# Peripheral.net
KiCad netlist of a schematic drawn in Altium Designer
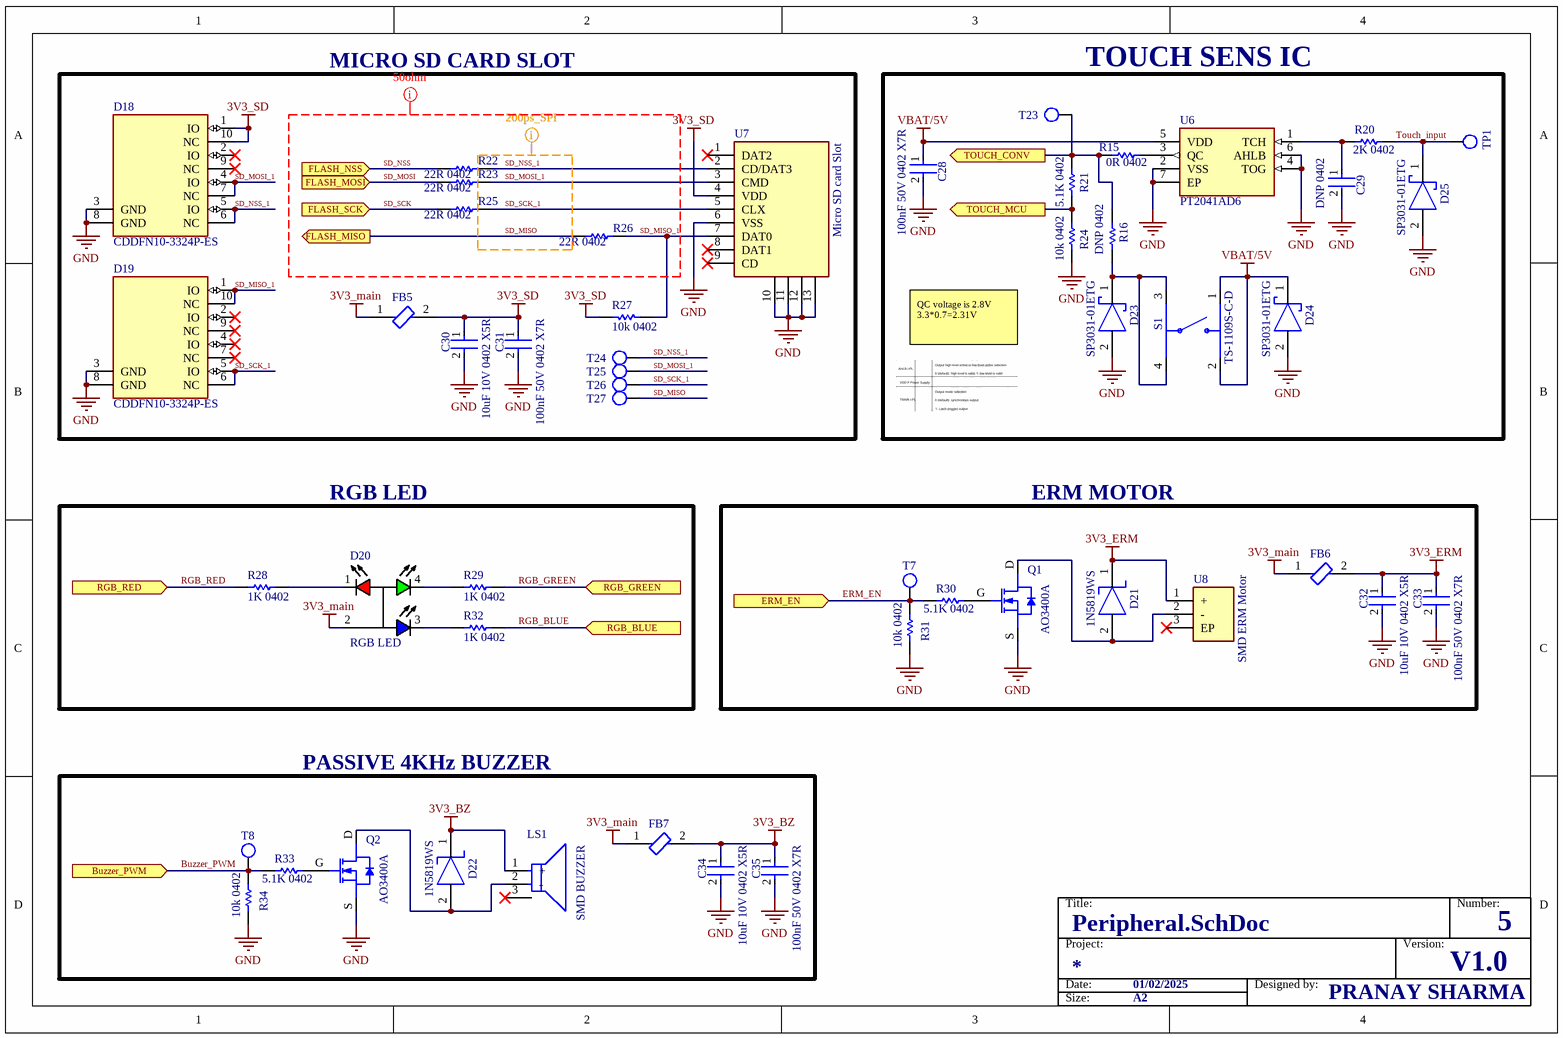
[diagram p0: Peripheral.SchDoc]

(export (version "E")
  (design (tool "Eeschema 10.0.6"))
  (components
    (comp (ref "C28")
      (value "100nF 50V 0402 X7R")
      (footprint "Res, Cap, Ind, LED, FB_Lib:0402 IPC CLASS C CAPACITOR")
      (libsource (lib "Capacitor_Lib") (part "100nF 50V 0402 X7R"))
    )
    (comp (ref "C29")
      (value "DNP 0402")
      (footprint "0402 IPC Class C Capacitor")
      (libsource (lib "Integrated Library V1.0") (part "Capacitor 0402"))
    )
    (comp (ref "C30")
      (value "10uF 10V 0402 X5R")
      (footprint "Res, Cap, Ind, LED, FB_Lib:0402 IPC CLASS C CAPACITOR")
      (libsource (lib "Capacitor_Lib") (part "10uF 10V 0402 X5R"))
    )
    (comp (ref "C31")
      (value "100nF 50V 0402 X7R")
      (footprint "Res, Cap, Ind, LED, FB_Lib:0402 IPC CLASS C CAPACITOR")
      (libsource (lib "Capacitor_Lib") (part "100nF 50V 0402 X7R"))
    )
    (comp (ref "C32")
      (value "10uF 10V 0402 X5R")
      (footprint "Res, Cap, Ind, LED, FB_Lib:0402 IPC CLASS C CAPACITOR")
      (libsource (lib "Capacitor_Lib") (part "10uF 10V 0402 X5R"))
    )
    (comp (ref "C33")
      (value "100nF 50V 0402 X7R")
      (footprint "Res, Cap, Ind, LED, FB_Lib:0402 IPC CLASS C CAPACITOR")
      (libsource (lib "Capacitor_Lib") (part "100nF 50V 0402 X7R"))
    )
    (comp (ref "C34")
      (value "10uF 10V 0402 X5R")
      (footprint "Res, Cap, Ind, LED, FB_Lib:0402 IPC CLASS C CAPACITOR")
      (libsource (lib "Capacitor_Lib") (part "10uF 10V 0402 X5R"))
    )
    (comp (ref "C35")
      (value "100nF 50V 0402 X7R")
      (footprint "Res, Cap, Ind, LED, FB_Lib:0402 IPC CLASS C CAPACITOR")
      (libsource (lib "Capacitor_Lib") (part "100nF 50V 0402 X7R"))
    )
    (comp (ref "D18")
      (value "CDDFN10-3324P-ES")
      (footprint "Res, Cap, Ind, LED, FB_Lib:DFN2510D-10 IPC-C")
      (libsource (lib "Diodes_Lib") (part "CDDFN10-3324P-ES"))
    )
    (comp (ref "D19")
      (value "CDDFN10-3324P-ES")
      (footprint "Res, Cap, Ind, LED, FB_Lib:DFN2510D-10 IPC-C")
      (libsource (lib "Diodes_Lib") (part "CDDFN10-3324P-ES"))
    )
    (comp (ref "D20")
      (value "RGB LED")
      (footprint "Res, Cap, Ind, LED, FB_Lib:NH-B1515RGBA-HF IPC-C")
      (libsource (lib "Diodes_Lib") (part "NH-B1515RGBA-HF"))
    )
    (comp (ref "D21")
      (value "1N5819WS")
      (footprint "Res, Cap, Ind, LED, FB_Lib:SOD-323 IPC-C")
      (libsource (lib "Diodes_Lib") (part "1N5819WS"))
    )
    (comp (ref "D22")
      (value "1N5819WS")
      (footprint "Res, Cap, Ind, LED, FB_Lib:SOD-323 IPC-C")
      (libsource (lib "Diodes_Lib") (part "1N5819WS"))
    )
    (comp (ref "D23")
      (value "SP3031-01ETG")
      (footprint "Res, Cap, Ind, LED, FB_Lib:SOD882 IPC-C")
      (libsource (lib "Diodes_Lib") (part "SP3031-01ETG"))
    )
    (comp (ref "D24")
      (value "SP3031-01ETG")
      (footprint "Res, Cap, Ind, LED, FB_Lib:SOD882 IPC-C")
      (libsource (lib "Diodes_Lib") (part "SP3031-01ETG"))
    )
    (comp (ref "D25")
      (value "SP3031-01ETG")
      (footprint "Res, Cap, Ind, LED, FB_Lib:SOD882 IPC-C")
      (libsource (lib "Diodes_Lib") (part "SP3031-01ETG"))
    )
    (comp (ref "FB5")
      (value "BLM15AX102SN1D")
      (footprint "Res, Cap, Ind, LED, FB_Lib:0402 IPC CLASS C FERRITE BEAD")
      (libsource (lib "Ferrite_Bead_Lib") (part "BLM15AX102SN1D"))
    )
    (comp (ref "FB6")
      (value "BLM15AX102SN1D")
      (footprint "Res, Cap, Ind, LED, FB_Lib:0402 IPC CLASS C FERRITE BEAD")
      (libsource (lib "Ferrite_Bead_Lib") (part "BLM15AX102SN1D"))
    )
    (comp (ref "FB7")
      (value "BLM15AX102SN1D")
      (footprint "Res, Cap, Ind, LED, FB_Lib:0402 IPC CLASS C FERRITE BEAD")
      (libsource (lib "Ferrite_Bead_Lib") (part "BLM15AX102SN1D"))
    )
    (comp (ref "LS1")
      (value "SMD BUZZER")
      (footprint "Miscellaneous_Lib:MLT-5020")
      (libsource (lib "Miscellaneous_Lib") (part "MLT-5020"))
    )
    (comp (ref "Q1")
      (value "AO3400A")
      (footprint "Transistors_Lib:SOT-23 IPC-C")
      (libsource (lib "Transistors_Lib") (part "AO3400A"))
    )
    (comp (ref "Q2")
      (value "AO3400A")
      (footprint "Transistors_Lib:SOT-23 IPC-C")
      (libsource (lib "Transistors_Lib") (part "AO3400A"))
    )
    (comp (ref "R15")
      (value "0R 0402")
      (footprint "Res, Cap, Ind, LED, FB_Lib:0402 IPC CLASS B RESISTOR")
      (libsource (lib "Resistor_Lib") (part "0R 1% 0402"))
    )
    (comp (ref "R16")
      (value "DNP 0402")
      (footprint "Res, Cap, Ind, LED, FB_Lib:0402 IPC CLASS B RESISTOR")
      (libsource (lib "Resistor_Lib") (part "0R 1% 0402"))
    )
    (comp (ref "R20")
      (value "2K 0402")
      (footprint "Res, Cap, Ind, LED, FB_Lib:0402 IPC CLASS C RESISTOR")
      (libsource (lib "Resistor_Lib") (part "2K 1% 0402"))
    )
    (comp (ref "R21")
      (value "5.1K 0402")
      (footprint "Res, Cap, Ind, LED, FB_Lib:0402 IPC CLASS C RESISTOR")
      (libsource (lib "Resistor_Lib") (part "5.1K 1% 0402"))
    )
    (comp (ref "R22")
      (value "22R 0402")
      (footprint "Res, Cap, Ind, LED, FB_Lib:0402 IPC CLASS C RESISTOR")
      (libsource (lib "Resistor_Lib") (part "22R 1% 0402"))
    )
    (comp (ref "R23")
      (value "22R 0402")
      (footprint "Res, Cap, Ind, LED, FB_Lib:0402 IPC CLASS C RESISTOR")
      (libsource (lib "Resistor_Lib") (part "22R 1% 0402"))
    )
    (comp (ref "R24")
      (value "10k 0402")
      (footprint "Res, Cap, Ind, LED, FB_Lib:0402 IPC CLASS C RESISTOR")
      (libsource (lib "Resistor_Lib") (part "10k 1% 0402"))
    )
    (comp (ref "R25")
      (value "22R 0402")
      (footprint "Res, Cap, Ind, LED, FB_Lib:0402 IPC CLASS C RESISTOR")
      (libsource (lib "Resistor_Lib") (part "22R 1% 0402"))
    )
    (comp (ref "R26")
      (value "22R 0402")
      (footprint "Res, Cap, Ind, LED, FB_Lib:0402 IPC CLASS C RESISTOR")
      (libsource (lib "Resistor_Lib") (part "22R 1% 0402"))
    )
    (comp (ref "R27")
      (value "10k 0402")
      (footprint "Res, Cap, Ind, LED, FB_Lib:0402 IPC CLASS C RESISTOR")
      (libsource (lib "Resistor_Lib") (part "10k 1% 0402"))
    )
    (comp (ref "R28")
      (value "1K 0402")
      (footprint "Res, Cap, Ind, LED, FB_Lib:0402 IPC CLASS C RESISTOR")
      (libsource (lib "Resistor_Lib") (part "1K 1% 0402"))
    )
    (comp (ref "R29")
      (value "1K 0402")
      (footprint "Res, Cap, Ind, LED, FB_Lib:0402 IPC CLASS C RESISTOR")
      (libsource (lib "Resistor_Lib") (part "1K 1% 0402"))
    )
    (comp (ref "R30")
      (value "5.1K 0402")
      (footprint "Res, Cap, Ind, LED, FB_Lib:0402 IPC CLASS C RESISTOR")
      (libsource (lib "Resistor_Lib") (part "5.1K 1% 0402"))
    )
    (comp (ref "R31")
      (value "10k 0402")
      (footprint "Res, Cap, Ind, LED, FB_Lib:0402 IPC CLASS C RESISTOR")
      (libsource (lib "Resistor_Lib") (part "10k 1% 0402"))
    )
    (comp (ref "R32")
      (value "1K 0402")
      (footprint "Res, Cap, Ind, LED, FB_Lib:0402 IPC CLASS C RESISTOR")
      (libsource (lib "Resistor_Lib") (part "1K 1% 0402"))
    )
    (comp (ref "R33")
      (value "5.1K 0402")
      (footprint "Res, Cap, Ind, LED, FB_Lib:0402 IPC CLASS C RESISTOR")
      (libsource (lib "Resistor_Lib") (part "5.1K 1% 0402"))
    )
    (comp (ref "R34")
      (value "10k 0402")
      (footprint "Res, Cap, Ind, LED, FB_Lib:0402 IPC CLASS C RESISTOR")
      (libsource (lib "Resistor_Lib") (part "10k 1% 0402"))
    )
    (comp (ref "S1")
      (value "TS-1109S-C-D")
      (footprint "TS-1127-C")
      (libsource (lib "Integrated Library V1.0") (part "TS-1127-C"))
    )
    (comp (ref "T7")
      (value "~")
      (footprint "Test Point TH")
      (libsource (lib "Miscellaneous_Lib") (part "Test Point TH"))
    )
    (comp (ref "T8")
      (value "~")
      (footprint "Test Point TH")
      (libsource (lib "Miscellaneous_Lib") (part "Test Point TH"))
    )
    (comp (ref "T23")
      (value "TP")
      (footprint "Miscellaneous_Lib:Testpoint1")
      (libsource (lib "Miscellaneous_Lib") (part "Testpoint1"))
    )
    (comp (ref "T24")
      (value "TP")
      (footprint "Miscellaneous_Lib:Testpoint1")
      (libsource (lib "Miscellaneous_Lib") (part "Testpoint1"))
    )
    (comp (ref "T25")
      (value "TP")
      (footprint "Miscellaneous_Lib:Testpoint1")
      (libsource (lib "Miscellaneous_Lib") (part "Testpoint1"))
    )
    (comp (ref "T26")
      (value "TP")
      (footprint "Miscellaneous_Lib:Testpoint1")
      (libsource (lib "Miscellaneous_Lib") (part "Testpoint1"))
    )
    (comp (ref "T27")
      (value "TP")
      (footprint "Miscellaneous_Lib:Testpoint1")
      (libsource (lib "Miscellaneous_Lib") (part "Testpoint1"))
    )
    (comp (ref "TP1")
      (value "Test Point TH")
      (footprint "Test Point TH")
      (libsource (lib "Integrated Library V1.0") (part "Test Point TH"))
    )
    (comp (ref "U6")
      (value "PT2041AD6")
      (footprint "Integrated_Circuits_Lib:DFN2X2-6L IPC-C")
      (libsource (lib "Integrated_Circuits_Lib") (part "PT2041AD6"))
    )
    (comp (ref "U7")
      (value "Micro SD card Slot")
      (footprint "Connectors_Lib:XKTF-015-G")
      (libsource (lib "Connectors_Lib") (part "XKTF-015-G"))
    )
    (comp (ref "U8")
      (value "SMD ERM Motor")
      (footprint "Miscellaneous_Lib:Z3OC1T8219731")
      (libsource (lib "Miscellaneous_Lib") (part "Z3OC1T8219731"))
    )
  )
  (nets
    (net (code "1") (name "/Buzzer_PWM") (class "Default")
      (node (ref "R33") (pin "1") (pinfunction "1_1") (pintype "passive"))
      (node (ref "R34") (pin "2") (pinfunction "2_2") (pintype "passive"))
      (node (ref "T8") (pin "0") (pinfunction "0_0") (pintype "passive"))
    )
    (net (code "2") (name "/ERM_EN") (class "Default")
      (node (ref "R30") (pin "1") (pinfunction "1_1") (pintype "passive"))
      (node (ref "R31") (pin "2") (pinfunction "2_2") (pintype "passive"))
      (node (ref "T7") (pin "0") (pinfunction "0_0") (pintype "passive"))
    )
    (net (code "3") (name "/RGB_BLUE") (class "Default")
      (node (ref "R32") (pin "2") (pinfunction "2_2") (pintype "passive"))
    )
    (net (code "4") (name "/RGB_GREEN") (class "Default")
      (node (ref "R29") (pin "2") (pinfunction "2_2") (pintype "passive"))
    )
    (net (code "5") (name "/RGB_RED") (class "Default")
      (node (ref "R28") (pin "1") (pinfunction "1_1") (pintype "passive"))
    )
    (net (code "6") (name "/SD_MISO") (class "Default")
      (node (ref "R26") (pin "1") (pinfunction "1_1") (pintype "passive"))
      (node (ref "T27") (pin "0") (pinfunction "0_0") (pintype "passive"))
    )
    (net (code "7") (name "/SD_MISO_1") (class "Default")
      (node (ref "D19") (pin "1") (pinfunction "IO_1") (pintype "bidirectional"))
      (node (ref "D19") (pin "10") (pinfunction "NC_10") (pintype "passive"))
      (node (ref "R26") (pin "2") (pinfunction "2_2") (pintype "passive"))
      (node (ref "R27") (pin "2") (pinfunction "2_2") (pintype "passive"))
      (node (ref "U7") (pin "7") (pinfunction "DAT0_7") (pintype "passive"))
    )
    (net (code "8") (name "/SD_MOSI") (class "Default")
      (node (ref "R23") (pin "1") (pinfunction "1_1") (pintype "passive"))
    )
    (net (code "9") (name "/SD_MOSI_1") (class "Default")
      (node (ref "D18") (pin "4") (pinfunction "IO_4") (pintype "bidirectional"))
      (node (ref "D18") (pin "7") (pinfunction "NC_7") (pintype "passive"))
      (node (ref "R23") (pin "2") (pinfunction "2_2") (pintype "passive"))
      (node (ref "T25") (pin "0") (pinfunction "0_0") (pintype "passive"))
      (node (ref "U7") (pin "3") (pinfunction "CMD_3") (pintype "passive"))
    )
    (net (code "10") (name "/SD_NSS") (class "Default")
      (node (ref "R22") (pin "1") (pinfunction "1_1") (pintype "passive"))
    )
    (net (code "11") (name "/SD_NSS_1") (class "Default")
      (node (ref "D18") (pin "5") (pinfunction "IO_5") (pintype "bidirectional"))
      (node (ref "D18") (pin "6") (pinfunction "NC_6") (pintype "passive"))
      (node (ref "R22") (pin "2") (pinfunction "2_2") (pintype "passive"))
      (node (ref "T24") (pin "0") (pinfunction "0_0") (pintype "passive"))
      (node (ref "U7") (pin "2") (pinfunction "CD/DAT3_2") (pintype "passive"))
    )
    (net (code "12") (name "/SD_SCK") (class "Default")
      (node (ref "R25") (pin "1") (pinfunction "1_1") (pintype "passive"))
    )
    (net (code "13") (name "/SD_SCK_1") (class "Default")
      (node (ref "D19") (pin "5") (pinfunction "IO_5") (pintype "bidirectional"))
      (node (ref "D19") (pin "6") (pinfunction "NC_6") (pintype "passive"))
      (node (ref "R25") (pin "2") (pinfunction "2_2") (pintype "passive"))
      (node (ref "T26") (pin "0") (pinfunction "0_0") (pintype "passive"))
      (node (ref "U7") (pin "5") (pinfunction "CLX_5") (pintype "passive"))
    )
    (net (code "14") (name "/TOUCH_CONV") (class "Default")
      (node (ref "R15") (pin "2") (pinfunction "2_2") (pintype "passive"))
      (node (ref "R16") (pin "1") (pinfunction "1_1") (pintype "passive"))
      (node (ref "R21") (pin "2") (pinfunction "2_2") (pintype "passive"))
      (node (ref "T23") (pin "0") (pinfunction "0_0") (pintype "passive"))
    )
    (net (code "15") (name "/TOUCH_MCU") (class "Default")
      (node (ref "R21") (pin "1") (pinfunction "1_1") (pintype "passive"))
      (node (ref "R24") (pin "1") (pinfunction "1_1") (pintype "passive"))
    )
    (net (code "16") (name "/Touch_input") (class "Default")
      (node (ref "D25") (pin "1") (pinfunction "C_1") (pintype "passive"))
      (node (ref "R20") (pin "2") (pinfunction "2_2") (pintype "passive"))
      (node (ref "TP1") (pin "0") (pinfunction "0_0") (pintype "passive"))
    )
    (net (code "17") (name "3V3_BZ") (class "Default")
      (node (ref "C34") (pin "1") (pinfunction "1_1") (pintype "passive"))
      (node (ref "C35") (pin "1") (pinfunction "1_1") (pintype "passive"))
      (node (ref "D22") (pin "1") (pinfunction "C_1") (pintype "passive"))
      (node (ref "FB7") (pin "2") (pinfunction "2_2") (pintype "passive"))
      (node (ref "LS1") (pin "1") (pinfunction "+_1") (pintype "passive"))
    )
    (net (code "18") (name "3V3_ERM") (class "Default")
      (node (ref "C32") (pin "1") (pinfunction "1_1") (pintype "passive"))
      (node (ref "C33") (pin "1") (pinfunction "1_1") (pintype "passive"))
      (node (ref "D21") (pin "1") (pinfunction "C_1") (pintype "passive"))
      (node (ref "FB6") (pin "2") (pinfunction "2_2") (pintype "passive"))
      (node (ref "U8") (pin "1") (pinfunction "+_1") (pintype "power_in"))
    )
    (net (code "19") (name "3V3_SD") (class "Default")
      (node (ref "C30") (pin "1") (pinfunction "1_1") (pintype "passive"))
      (node (ref "C31") (pin "1") (pinfunction "1_1") (pintype "passive"))
      (node (ref "D18") (pin "1") (pinfunction "IO_1") (pintype "bidirectional"))
      (node (ref "D18") (pin "10") (pinfunction "NC_10") (pintype "passive"))
      (node (ref "FB5") (pin "2") (pinfunction "2_2") (pintype "passive"))
      (node (ref "R27") (pin "1") (pinfunction "1_1") (pintype "passive"))
      (node (ref "U7") (pin "4") (pinfunction "VDD_4") (pintype "passive"))
    )
    (net (code "20") (name "3V3_main") (class "Default")
      (node (ref "D20") (pin "2") (pinfunction "COM+_2") (pintype "passive"))
      (node (ref "FB5") (pin "1") (pinfunction "1_1") (pintype "passive"))
      (node (ref "FB6") (pin "1") (pinfunction "1_1") (pintype "passive"))
      (node (ref "FB7") (pin "1") (pinfunction "1_1") (pintype "passive"))
    )
    (net (code "21") (name "GND") (class "Default")
      (node (ref "C28") (pin "2") (pinfunction "2_2") (pintype "passive"))
      (node (ref "C29") (pin "2") (pinfunction "2_2") (pintype "passive"))
      (node (ref "C30") (pin "2") (pinfunction "2_2") (pintype "passive"))
      (node (ref "C31") (pin "2") (pinfunction "2_2") (pintype "passive"))
      (node (ref "C32") (pin "2") (pinfunction "2_2") (pintype "passive"))
      (node (ref "C33") (pin "2") (pinfunction "2_2") (pintype "passive"))
      (node (ref "C34") (pin "2") (pinfunction "2_2") (pintype "passive"))
      (node (ref "C35") (pin "2") (pinfunction "2_2") (pintype "passive"))
      (node (ref "D18") (pin "3") (pinfunction "GND_3") (pintype "power_in"))
      (node (ref "D18") (pin "8") (pinfunction "GND_8") (pintype "power_in"))
      (node (ref "D19") (pin "3") (pinfunction "GND_3") (pintype "power_in"))
      (node (ref "D19") (pin "8") (pinfunction "GND_8") (pintype "power_in"))
      (node (ref "D23") (pin "2") (pinfunction "A_2") (pintype "passive"))
      (node (ref "D24") (pin "2") (pinfunction "A_2") (pintype "passive"))
      (node (ref "D25") (pin "2") (pinfunction "A_2") (pintype "passive"))
      (node (ref "Q1") (pin "S") (pinfunction "SOURCE_S") (pintype "passive"))
      (node (ref "Q2") (pin "S") (pinfunction "SOURCE_S") (pintype "passive"))
      (node (ref "R24") (pin "2") (pinfunction "2_2") (pintype "passive"))
      (node (ref "R31") (pin "1") (pinfunction "1_1") (pintype "passive"))
      (node (ref "R34") (pin "1") (pinfunction "1_1") (pintype "passive"))
      (node (ref "U6") (pin "2") (pinfunction "VSS_2") (pintype "power_in"))
      (node (ref "U6") (pin "4") (pinfunction "TOG_4") (pintype "input"))
      (node (ref "U6") (pin "6") (pinfunction "AHLB_6") (pintype "input"))
      (node (ref "U6") (pin "7") (pinfunction "EP_7") (pintype "power_in"))
      (node (ref "U7") (pin "10") (pintype "passive"))
      (node (ref "U7") (pin "11") (pintype "passive"))
      (node (ref "U7") (pin "12") (pintype "passive"))
      (node (ref "U7") (pin "13") (pintype "passive"))
      (node (ref "U7") (pin "6") (pinfunction "VSS_6") (pintype "passive"))
    )
    (net (code "22") (name "Net-(D20-B-)") (class "Default")
      (node (ref "D20") (pin "3") (pinfunction "B-_3") (pintype "passive"))
      (node (ref "R32") (pin "1") (pinfunction "1_1") (pintype "passive"))
    )
    (net (code "23") (name "Net-(D20-G-)") (class "Default")
      (node (ref "D20") (pin "4") (pinfunction "G-_4") (pintype "passive"))
      (node (ref "R29") (pin "1") (pinfunction "1_1") (pintype "passive"))
    )
    (net (code "24") (name "Net-(D20-R-)") (class "Default")
      (node (ref "D20") (pin "1") (pinfunction "R-_1") (pintype "passive"))
      (node (ref "R28") (pin "2") (pinfunction "2_2") (pintype "passive"))
    )
    (net (code "25") (name "Net-(D21-A)") (class "Default")
      (node (ref "D21") (pin "2") (pinfunction "A_2") (pintype "passive"))
      (node (ref "Q1") (pin "D") (pinfunction "DRAIN_D") (pintype "passive"))
      (node (ref "U8") (pin "2") (pinfunction "-_2") (pintype "power_in"))
    )
    (net (code "26") (name "Net-(D22-A)") (class "Default")
      (node (ref "D22") (pin "2") (pinfunction "A_2") (pintype "passive"))
      (node (ref "LS1") (pin "2") (pinfunction "-_2") (pintype "passive"))
      (node (ref "Q2") (pin "D") (pinfunction "DRAIN_D") (pintype "passive"))
    )
    (net (code "27") (name "Net-(D23-C)") (class "Default")
      (node (ref "D23") (pin "1") (pinfunction "C_1") (pintype "passive"))
      (node (ref "R16") (pin "2") (pinfunction "2_2") (pintype "passive"))
      (node (ref "S1") (pin "3") (pinfunction "3_3") (pintype "passive"))
      (node (ref "S1") (pin "4") (pinfunction "4_4") (pintype "passive"))
    )
    (net (code "28") (name "Net-(Q1-GATE)") (class "Default")
      (node (ref "Q1") (pin "G") (pinfunction "GATE_G") (pintype "passive"))
      (node (ref "R30") (pin "2") (pinfunction "2_2") (pintype "passive"))
    )
    (net (code "29") (name "Net-(Q2-GATE)") (class "Default")
      (node (ref "Q2") (pin "G") (pinfunction "GATE_G") (pintype "passive"))
      (node (ref "R33") (pin "2") (pinfunction "2_2") (pintype "passive"))
    )
    (net (code "30") (name "Net-(U6-QC)") (class "Default")
      (node (ref "R15") (pin "1") (pinfunction "1_1") (pintype "passive"))
      (node (ref "U6") (pin "3") (pinfunction "QC_3") (pintype "output"))
    )
    (net (code "31") (name "Net-(U6-TCH)") (class "Default")
      (node (ref "C29") (pin "1") (pinfunction "1_1") (pintype "passive"))
      (node (ref "R20") (pin "1") (pinfunction "1_1") (pintype "passive"))
      (node (ref "U6") (pin "1") (pinfunction "TCH_1") (pintype "input"))
    )
    (net (code "32") (name "VBAT{slash}5V") (class "Default")
      (node (ref "C28") (pin "1") (pinfunction "1_1") (pintype "passive"))
      (node (ref "D24") (pin "1") (pinfunction "C_1") (pintype "passive"))
      (node (ref "S1") (pin "1") (pinfunction "1_1") (pintype "passive"))
      (node (ref "S1") (pin "2") (pinfunction "2_2") (pintype "passive"))
      (node (ref "U6") (pin "5") (pinfunction "VDD_5") (pintype "power_in"))
    )
    (net (code "33") (name "unconnected-(D18-IO-Pad2)") (class "Default")
      (node (ref "D18") (pin "2") (pinfunction "IO_2") (pintype "bidirectional+no_connect"))
    )
    (net (code "34") (name "unconnected-(D18-NC-Pad9)") (class "Default")
      (node (ref "D18") (pin "9") (pinfunction "NC_9") (pintype "passive+no_connect"))
    )
    (net (code "35") (name "unconnected-(D19-IO-Pad2)") (class "Default")
      (node (ref "D19") (pin "2") (pinfunction "IO_2") (pintype "bidirectional+no_connect"))
    )
    (net (code "36") (name "unconnected-(D19-IO-Pad4)") (class "Default")
      (node (ref "D19") (pin "4") (pinfunction "IO_4") (pintype "bidirectional+no_connect"))
    )
    (net (code "37") (name "unconnected-(D19-NC-Pad7)") (class "Default")
      (node (ref "D19") (pin "7") (pinfunction "NC_7") (pintype "passive+no_connect"))
    )
    (net (code "38") (name "unconnected-(D19-NC-Pad9)") (class "Default")
      (node (ref "D19") (pin "9") (pinfunction "NC_9") (pintype "passive+no_connect"))
    )
    (net (code "39") (name "unconnected-(LS1-A-Pad3)") (class "Default")
      (node (ref "LS1") (pin "3") (pinfunction "A_3") (pintype "passive+no_connect"))
    )
    (net (code "40") (name "unconnected-(U7-CD-Pad9)") (class "Default")
      (node (ref "U7") (pin "9") (pinfunction "CD_9") (pintype "passive+no_connect"))
    )
    (net (code "41") (name "unconnected-(U7-DAT1-Pad8)") (class "Default")
      (node (ref "U7") (pin "8") (pinfunction "DAT1_8") (pintype "passive+no_connect"))
    )
    (net (code "42") (name "unconnected-(U7-DAT2-Pad1)") (class "Default")
      (node (ref "U7") (pin "1") (pinfunction "DAT2_1") (pintype "passive+no_connect"))
    )
    (net (code "43") (name "unconnected-(U8-EP-Pad3)") (class "Default")
      (node (ref "U8") (pin "3") (pinfunction "EP_3") (pintype "passive+no_connect"))
    )
  )
)
